# MCU.net
KiCad netlist of a schematic drawn in Altium Designer
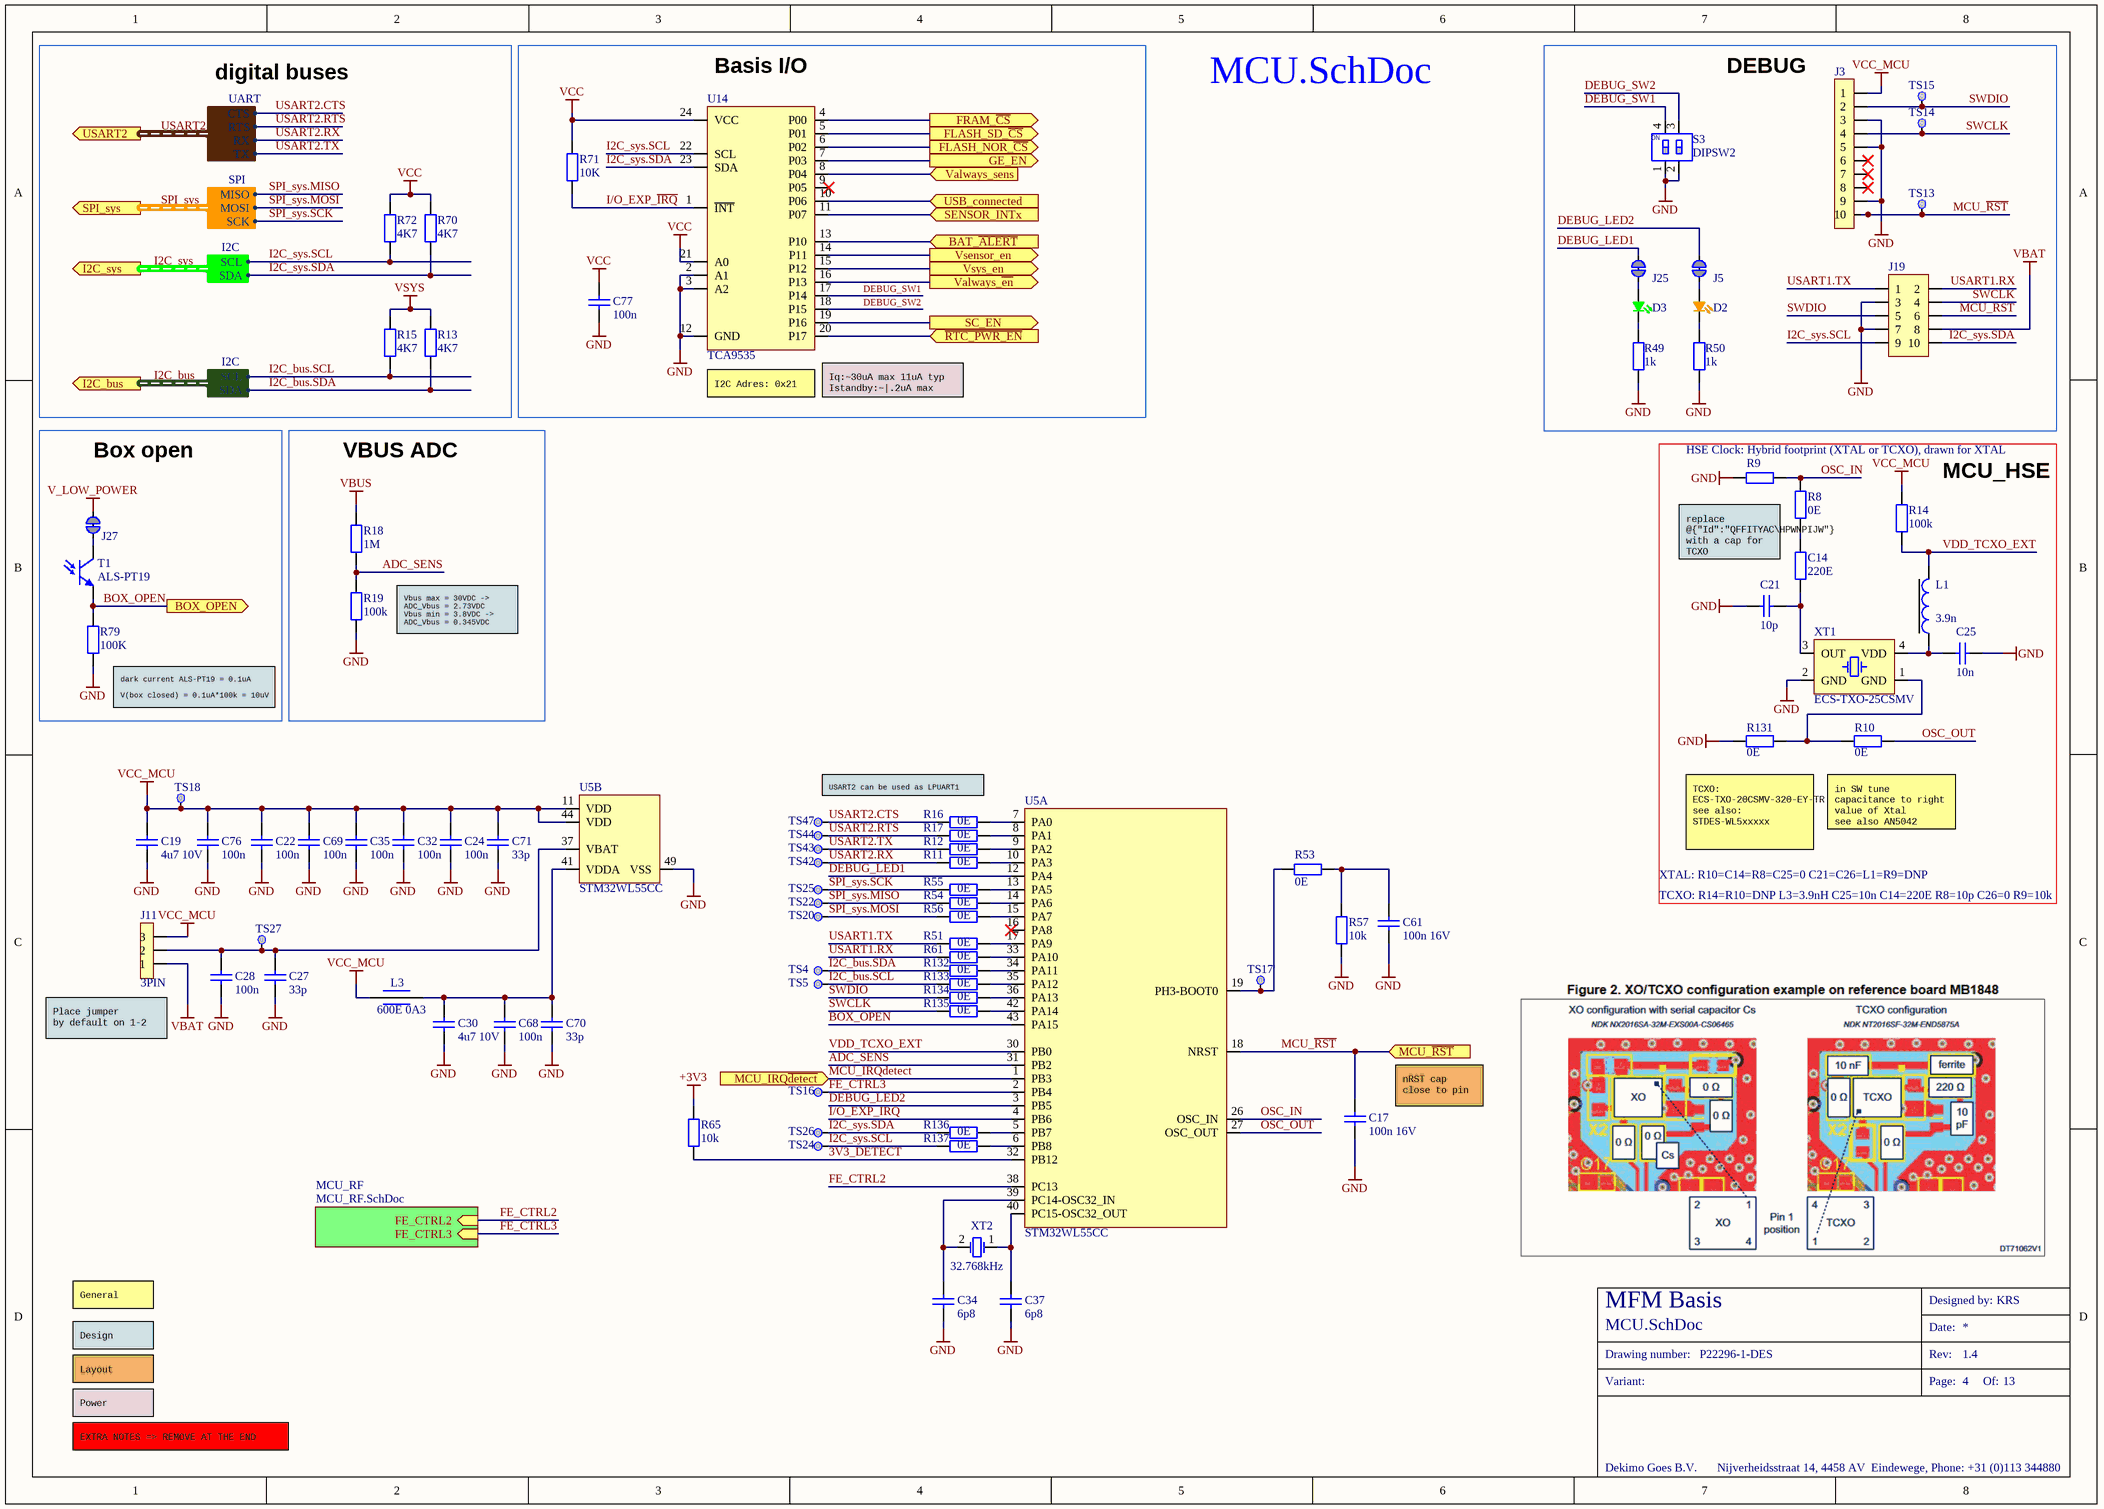
[diagram p0: MCU.SchDoc]

(export (version "E")
  (design (tool "Eeschema 10.0.6"))
  (components
    (comp (ref "C14")
      (value "220E")
      (footprint "RESC1005X04N")
      (description "220ohm 62.5mW 1%")
      (libsource (lib "") (part "Resistor_2"))
    )
    (comp (ref "C17")
      (value "100n 16V")
      (footprint "CAPC1005X05N")
      (description "100nF, 16V, 10%, X7R")
      (libsource (lib "DCI") (part "Capacitor_NP"))
    )
    (comp (ref "C19")
      (value "4u7 10V")
      (footprint "CAPC1608X09N")
      (description "4.7uF 10% 10V X5R")
      (libsource (lib "DCI") (part "Capacitor_NP"))
    )
    (comp (ref "C21")
      (value "10p")
      (footprint "CAPC1005X05N")
      (description "10pF, 50V, 5%, NP0")
      (libsource (lib "DCI") (part "Capacitor_NP"))
    )
    (comp (ref "C22")
      (value "100n")
      (footprint "CAPC1005X05N")
      (description "100nF, 16V, 10%, X7R")
      (libsource (lib "DCI") (part "Capacitor_NP"))
    )
    (comp (ref "C24")
      (value "100n")
      (footprint "CAP-000G001-002")
      (description "100nF, 10V, X5R")
      (libsource (lib "DCI") (part "Capacitor_NP"))
    )
    (comp (ref "C25")
      (value "10n")
      (footprint "CAP-000G001-002")
      (description "10nF, 10V, X7R")
      (libsource (lib "") (part "Capacitor_NP_1"))
    )
    (comp (ref "C27")
      (value "33p")
      (footprint "CAP-000G001-002")
      (description "33pF, 25V, 5%")
      (libsource (lib "DCI") (part "Capacitor_NP"))
    )
    (comp (ref "C28")
      (value "100n")
      (footprint "CAP-000G001-002")
      (description "100nF, 10V, X5R")
      (libsource (lib "DCI") (part "Capacitor_NP"))
    )
    (comp (ref "C30")
      (value "4u7 10V")
      (footprint "CAPC1608X09N")
      (description "4.7uF 10% 10V X5R")
      (libsource (lib "DCI") (part "Capacitor_NP"))
    )
    (comp (ref "C32")
      (value "100n")
      (footprint "CAPC1005X05N")
      (description "100nF, 16V, 10%, X7R")
      (libsource (lib "DCI") (part "Capacitor_NP"))
    )
    (comp (ref "C34")
      (value "6p8")
      (footprint "CAPC1608X09N")
      (description "6p8 +-0.5p 25V NP0")
      (libsource (lib "DCI") (part "Capacitor_NP"))
    )
    (comp (ref "C35")
      (value "100n")
      (footprint "CAPC1005X05N")
      (description "100nF, 16V, 10%, X7R")
      (libsource (lib "DCI") (part "Capacitor_NP"))
    )
    (comp (ref "C37")
      (value "6p8")
      (footprint "CAPC1608X09N")
      (description "6p8 +-0.5p 25V NP0")
      (libsource (lib "DCI") (part "Capacitor_NP"))
    )
    (comp (ref "C61")
      (value "100n 16V")
      (footprint "CAPC1005X05N")
      (description "100nF, 16V, 10%, X7R")
      (libsource (lib "DCI") (part "Capacitor_NP"))
    )
    (comp (ref "C68")
      (value "100n")
      (footprint "CAPC1005X05N")
      (description "100nF, 16V, 10%, X7R")
      (libsource (lib "DCI") (part "Capacitor_NP"))
    )
    (comp (ref "C69")
      (value "100n")
      (footprint "CAPC1005X05N")
      (description "100nF, 16V, 10%, X7R")
      (libsource (lib "DCI") (part "Capacitor_NP"))
    )
    (comp (ref "C70")
      (value "33p")
      (footprint "CAP-000G001-002")
      (description "33pF, 25V, 5%")
      (libsource (lib "DCI") (part "Capacitor_NP"))
    )
    (comp (ref "C71")
      (value "33p")
      (footprint "CAPC1005X05N")
      (description "33pF, 50V, 5%, COG")
      (libsource (lib "DCI") (part "Capacitor_NP"))
    )
    (comp (ref "C76")
      (value "100n")
      (footprint "CAPC1005X05N")
      (description "100nF, 16V, 10%, X7R")
      (libsource (lib "DCI") (part "Capacitor_NP"))
    )
    (comp (ref "C77")
      (value "100n")
      (footprint "CAPC1608X09N")
      (description "100nF 50V 10% X7R")
      (libsource (lib "DCI") (part "Capacitor_NP"))
    )
    (comp (ref "D2")
      (value "~")
      (footprint "LED_0603")
      (description "Led Orange 0603")
      (libsource (lib "DCI") (part "LED_AMBER"))
    )
    (comp (ref "D3")
      (value "~")
      (footprint "LED_0603_ANODE")
      (description "Led Groen 0603")
      (libsource (lib "DCI") (part "LED_GREEN"))
    )
    (comp (ref "J3")
      (value "Harwin Archer M50 Series")
      (footprint "PHDR2X5_SMD_P1.27")
      (description "pinh 2x5/straight/Au/1.27pitch")
      (libsource (lib "DCI") (part "10PIN"))
    )
    (comp (ref "J5")
      (value "~")
      (footprint "Solderbridge NC")
      (description "Solderbridge  - Normally Connected")
      (libsource (lib "PCBComponenten") (part "SolderbridgeNC"))
    )
    (comp (ref "J11")
      (value "3PIN")
      (footprint "CON-003G001-003")
      (description "pinh 1x3/straight/Au/1.27pitch")
      (libsource (lib "DCI") (part "3PIN"))
    )
    (comp (ref "J19")
      (value "~")
      (footprint "PHDR2X5_P2.54")
      (description "pinh 2x5/straight/h=6.7/Au")
      (libsource (lib "DCI") (part "2X5PIN"))
    )
    (comp (ref "J25")
      (value "~")
      (footprint "Solderbridge NC")
      (description "Solderbridge  - Normally Connected")
      (libsource (lib "PCBComponenten") (part "SolderbridgeNC"))
    )
    (comp (ref "J27")
      (value "~")
      (footprint "Solderbridge NC")
      (description "Solderbridge  - Normally Connected")
      (libsource (lib "PCBComponenten") (part "SolderbridgeNC"))
    )
    (comp (ref "L1")
      (value "3.9n")
      (footprint "IND-002G000-002")
      (description "3.9nH 0.1nH 750mA")
      (libsource (lib "DCI") (part "Inductor"))
    )
    (comp (ref "L3")
      (value "600E 0A3")
      (footprint "INDC1608X10N")
      (description "600E @100Mhz 0.3A")
      (libsource (lib "DCI") (part "ferrite"))
    )
    (comp (ref "R8")
      (value "0E")
      (footprint "RESC1005X04N")
      (description "0E, 62.5mW, 1%")
      (libsource (lib "DCI") (part "Resistor"))
    )
    (comp (ref "R9")
      (value "100E")
      (footprint "RESC1005X04N")
      (description "100E, 62.5mW, 1%")
      (libsource (lib "") (part "Resistor_1"))
    )
    (comp (ref "R10")
      (value "0E")
      (footprint "RESC1005X04N")
      (description "0E, 62.5mW, 1%")
      (libsource (lib "") (part "Resistor_1"))
    )
    (comp (ref "R11")
      (value "0E")
      (footprint "RESC1005X04N")
      (description "0E, 62.5mW, 1%")
      (libsource (lib "") (part "Resistor_1"))
    )
    (comp (ref "R12")
      (value "0E")
      (footprint "RESC1005X04N")
      (description "0E, 62.5mW, 1%")
      (libsource (lib "") (part "Resistor_1"))
    )
    (comp (ref "R13")
      (value "4K7")
      (footprint "RESC1005x04N")
      (description "4K7, 62.5mW, 1%")
      (libsource (lib "DCI") (part "Resistor"))
    )
    (comp (ref "R14")
      (value "100k")
      (footprint "RESC1005X04N")
      (description "100K, 62.5mW, 1%")
      (libsource (lib "DCI") (part "Resistor"))
    )
    (comp (ref "R15")
      (value "4K7")
      (footprint "RESC1005x04N")
      (description "4K7, 62.5mW, 1%")
      (libsource (lib "DCI") (part "Resistor"))
    )
    (comp (ref "R16")
      (value "0E")
      (footprint "RESC1005X04N")
      (description "0E, 62.5mW, 1%")
      (libsource (lib "") (part "Resistor_1"))
    )
    (comp (ref "R17")
      (value "0E")
      (footprint "RESC1005X04N")
      (description "0E, 62.5mW, 1%")
      (libsource (lib "") (part "Resistor_1"))
    )
    (comp (ref "R18")
      (value "1M")
      (footprint "RESC1005x04N")
      (description "1M, 62.5mW, 1%")
      (libsource (lib "") (part "Resistor_4"))
    )
    (comp (ref "R19")
      (value "100k")
      (footprint "RESC1005X04N")
      (description "100K, 62.5mW, 1%")
      (libsource (lib "DCI") (part "Resistor"))
    )
    (comp (ref "R49")
      (value "1k")
      (footprint "RESC1608X13N")
      (description "1K, 100mW, 1%")
      (libsource (lib "") (part "Resistor_2"))
    )
    (comp (ref "R50")
      (value "1k")
      (footprint "RESC1608X13N")
      (description "1K, 100mW, 1%")
      (libsource (lib "") (part "Resistor_2"))
    )
    (comp (ref "R51")
      (value "0E")
      (footprint "RESC1005X04N")
      (description "0E, 62.5mW, 1%")
      (libsource (lib "") (part "Resistor_1"))
    )
    (comp (ref "R53")
      (value "0E")
      (footprint "RESC1005X04N")
      (description "0E, 62.5mW, 1%")
      (libsource (lib "") (part "Resistor_3"))
    )
    (comp (ref "R54")
      (value "0E")
      (footprint "RESC1005X04N")
      (description "0E, 62.5mW, 1%")
      (libsource (lib "") (part "Resistor_1"))
    )
    (comp (ref "R55")
      (value "0E")
      (footprint "RESC1005X04N")
      (description "0E, 62.5mW, 1%")
      (libsource (lib "") (part "Resistor_1"))
    )
    (comp (ref "R56")
      (value "0E")
      (footprint "RESC1005X04N")
      (description "0E, 62.5mW, 1%")
      (libsource (lib "") (part "Resistor_1"))
    )
    (comp (ref "R57")
      (value "10k")
      (footprint "RESC1005X04N")
      (description "10K, 62.5mW, 1%")
      (libsource (lib "") (part "Resistor_1"))
    )
    (comp (ref "R61")
      (value "0E")
      (footprint "RESC1005X04N")
      (description "0E, 62.5mW, 1%")
      (libsource (lib "") (part "Resistor_1"))
    )
    (comp (ref "R65")
      (value "10k")
      (footprint "RESC1005X04N")
      (description "10K, 62.5mW, 1%")
      (libsource (lib "") (part "Resistor_1"))
    )
    (comp (ref "R70")
      (value "4K7")
      (footprint "RESC1005x04N")
      (description "4K7, 62.5mW, 1%")
      (libsource (lib "DCI") (part "Resistor"))
    )
    (comp (ref "R71")
      (value "10K")
      (footprint "RESC1608X13N")
      (description "10k 100mW, 1%")
      (libsource (lib "DCI") (part "Resistor"))
    )
    (comp (ref "R72")
      (value "4K7")
      (footprint "RESC1005x04N")
      (description "4K7, 62.5mW, 1%")
      (libsource (lib "DCI") (part "Resistor"))
    )
    (comp (ref "R79")
      (value "100K")
      (footprint "RESC1608X13N")
      (description "100k 100mW, 1%")
      (libsource (lib "DCI") (part "Resistor"))
    )
    (comp (ref "R131")
      (value "0E")
      (footprint "RESC1005X04N")
      (description "0E, 62.5mW, 1%")
      (libsource (lib "") (part "Resistor_1"))
    )
    (comp (ref "R132")
      (value "0E")
      (footprint "RESC1005X04N")
      (description "0E, 62.5mW, 1%")
      (libsource (lib "") (part "Resistor_1"))
    )
    (comp (ref "R133")
      (value "0E")
      (footprint "RESC1005X04N")
      (description "0E, 62.5mW, 1%")
      (libsource (lib "") (part "Resistor_1"))
    )
    (comp (ref "R134")
      (value "0E")
      (footprint "RESC1005X04N")
      (description "0E, 62.5mW, 1%")
      (libsource (lib "") (part "Resistor_1"))
    )
    (comp (ref "R135")
      (value "0E")
      (footprint "RESC1005X04N")
      (description "0E, 62.5mW, 1%")
      (libsource (lib "") (part "Resistor_1"))
    )
    (comp (ref "R136")
      (value "0E")
      (footprint "RESC1005X04N")
      (description "0E, 62.5mW, 1%")
      (libsource (lib "") (part "Resistor_1"))
    )
    (comp (ref "R137")
      (value "0E")
      (footprint "RESC1005X04N")
      (description "0E, 62.5mW, 1%")
      (libsource (lib "") (part "Resistor_1"))
    )
    (comp (ref "S3")
      (value "DIPSW2")
      (footprint "SW_GDH02S04")
      (description "DIP,2p,Straight,H=2,3mm,SMD,AU")
      (libsource (lib "DCI") (part "DIPSW2"))
    )
    (comp (ref "T1")
      (value "ALS-PT19")
      (footprint "SMD-000G001-002")
      (description "Ambient Light Sensor")
      (libsource (lib "DCI") (part "SENS_NPN_Photo"))
    )
    (comp (ref "TS4")
      (value "TESTPAD")
      (footprint "TESTPAD 2MM")
      (description "0.5mm Testpad SMD")
      (libsource (lib "PCBComponenten") (part "TESTPAD"))
    )
    (comp (ref "TS5")
      (value "TESTPAD")
      (footprint "TESTPAD 2MM")
      (description "0.5mm Testpad SMD")
      (libsource (lib "PCBComponenten") (part "TESTPAD"))
    )
    (comp (ref "TS13")
      (value "TESTPAD")
      (footprint "TESTPAD 2MM")
      (description "0.5mm Testpad SMD")
      (libsource (lib "PCBComponenten") (part "TESTPAD"))
    )
    (comp (ref "TS14")
      (value "TESTPAD")
      (footprint "TESTPAD 2MM")
      (description "0.5mm Testpad SMD")
      (libsource (lib "PCBComponenten") (part "TESTPAD"))
    )
    (comp (ref "TS15")
      (value "TESTPAD")
      (footprint "TESTPAD 2MM")
      (description "0.5mm Testpad SMD")
      (libsource (lib "PCBComponenten") (part "TESTPAD"))
    )
    (comp (ref "TS16")
      (value "TESTPAD")
      (footprint "TESTPAD 2MM")
      (description "0.5mm Testpad SMD")
      (libsource (lib "PCBComponenten") (part "TESTPAD"))
    )
    (comp (ref "TS17")
      (value "TESTPAD")
      (footprint "TESTPAD 2MM")
      (description "0.5mm Testpad SMD")
      (libsource (lib "PCBComponenten") (part "TESTPAD"))
    )
    (comp (ref "TS18")
      (value "TESTPAD")
      (footprint "TESTPAD 2MM")
      (description "0.5mm Testpad SMD")
      (libsource (lib "PCBComponenten") (part "TESTPAD"))
    )
    (comp (ref "TS20")
      (value "TESTPAD")
      (footprint "TESTPAD 2MM")
      (description "0.5mm Testpad SMD")
      (libsource (lib "PCBComponenten") (part "TESTPAD"))
    )
    (comp (ref "TS22")
      (value "TESTPAD")
      (footprint "TESTPAD 2MM")
      (description "0.5mm Testpad SMD")
      (libsource (lib "PCBComponenten") (part "TESTPAD"))
    )
    (comp (ref "TS24")
      (value "TESTPAD")
      (footprint "TESTPAD 2MM")
      (description "0.5mm Testpad SMD")
      (libsource (lib "PCBComponenten") (part "TESTPAD"))
    )
    (comp (ref "TS25")
      (value "TESTPAD")
      (footprint "TESTPAD 2MM")
      (description "0.5mm Testpad SMD")
      (libsource (lib "PCBComponenten") (part "TESTPAD"))
    )
    (comp (ref "TS26")
      (value "TESTPAD")
      (footprint "TESTPAD 2MM")
      (description "0.5mm Testpad SMD")
      (libsource (lib "PCBComponenten") (part "TESTPAD"))
    )
    (comp (ref "TS27")
      (value "TESTPAD")
      (footprint "TESTPAD 2MM")
      (description "0.5mm Testpad SMD")
      (libsource (lib "PCBComponenten") (part "TESTPAD"))
    )
    (comp (ref "TS42")
      (value "TESTPAD")
      (footprint "TESTPAD 2MM")
      (description "0.5mm Testpad SMD")
      (libsource (lib "PCBComponenten") (part "TESTPAD"))
    )
    (comp (ref "TS43")
      (value "TESTPAD")
      (footprint "TESTPAD 2MM")
      (description "0.5mm Testpad SMD")
      (libsource (lib "PCBComponenten") (part "TESTPAD"))
    )
    (comp (ref "TS44")
      (value "TESTPAD")
      (footprint "TESTPAD 2MM")
      (description "0.5mm Testpad SMD")
      (libsource (lib "PCBComponenten") (part "TESTPAD"))
    )
    (comp (ref "TS47")
      (value "TESTPAD")
      (footprint "TESTPAD 2MM")
      (description "0.5mm Testpad SMD")
      (libsource (lib "PCBComponenten") (part "TESTPAD"))
    )
    (comp (ref "U5")
      (value "STM32WL55CC")
      (footprint "QFN-500G000-048")
      (libsource (lib "DCI") (part "STM32WL55"))
    )
    (comp (ref "U14")
      (value "TCA9535")
      (footprint "SOP-650001-024")
      (description "16-bits  I2C I/O Expander")
      (libsource (lib "DCI") (part "IO_EXPANDER_TCA9535"))
    )
    (comp (ref "XT1")
      (value "ECS-TXO-25CSMV")
      (footprint "XTL-001G001-004")
      (description "32Mhz 1V7-3V465 2x1.6mm")
      (libsource (lib "DCI") (part "OSC_4P"))
    )
    (comp (ref "XT2")
      (value "32.768kHz")
      (footprint "CHIP2PINSM127P600-8N")
      (description "32.768kHz 20ppm 12.5pF")
      (libsource (lib "DCI") (part "XTAL"))
    )
  )
  (nets
    (net (code "5") (name "+3V3") (class "Default")
      (node (ref "R65") (pin "2") (pinfunction "2_2") (pintype "passive"))
    )
    (net (code "6") (name "/3V3_DETECT") (class "Default")
      (node (ref "R65") (pin "1") (pinfunction "1_1") (pintype "passive"))
      (node (ref "U5") (pin "32") (pinfunction "PB12_32") (pintype "passive"))
    )
    (net (code "7") (name "/ADC_SENS") (class "Default")
      (node (ref "R18") (pin "2") (pinfunction "2_2") (pintype "passive"))
      (node (ref "R19") (pin "2") (pinfunction "2_2") (pintype "passive"))
      (node (ref "U5") (pin "31") (pinfunction "PB2_31") (pintype "passive"))
    )
    (net (code "8") (name "/BAT_~{ALERT}") (class "Default")
      (node (ref "U14") (pin "13") (pinfunction "P10_13") (pintype "passive"))
    )
    (net (code "9") (name "/BOX_OPEN") (class "Default")
      (node (ref "R79") (pin "2") (pinfunction "2_2") (pintype "passive"))
      (node (ref "T1") (pin "2") (pinfunction "2_2") (pintype "passive"))
      (node (ref "U5") (pin "43") (pinfunction "PA15_43") (pintype "passive"))
    )
    (net (code "10") (name "/DEBUG_LED1") (class "Default")
      (node (ref "J25") (pin "2") (pinfunction "2_2") (pintype "passive"))
      (node (ref "U5") (pin "12") (pinfunction "PA4_12") (pintype "passive"))
    )
    (net (code "11") (name "/DEBUG_LED2") (class "Default")
      (node (ref "J5") (pin "2") (pinfunction "2_2") (pintype "passive"))
      (node (ref "U5") (pin "3") (pinfunction "PB5_3") (pintype "passive"))
    )
    (net (code "12") (name "/DEBUG_SW1") (class "Default")
      (node (ref "S3") (pin "4") (pinfunction "B1_4") (pintype "passive"))
      (node (ref "U14") (pin "17") (pinfunction "P14_17") (pintype "passive"))
    )
    (net (code "13") (name "/DEBUG_SW2") (class "Default")
      (node (ref "S3") (pin "3") (pinfunction "B2_3") (pintype "passive"))
      (node (ref "U14") (pin "18") (pinfunction "P15_18") (pintype "passive"))
    )
    (net (code "14") (name "/FE_CTRL2") (class "Default")
      (node (ref "U5") (pin "38") (pinfunction "PC13_38") (pintype "passive"))
    )
    (net (code "15") (name "/FE_CTRL3") (class "Default")
      (node (ref "TS16") (pin "1") (pinfunction "TP_1") (pintype "passive"))
      (node (ref "U5") (pin "2") (pinfunction "PB4_2") (pintype "passive"))
    )
    (net (code "16") (name "/FLASH_NOR_~{CS}") (class "Default")
      (node (ref "U14") (pin "6") (pinfunction "P02_6") (pintype "passive"))
    )
    (net (code "17") (name "/FLASH_SD_~{CS}") (class "Default")
      (node (ref "U14") (pin "5") (pinfunction "P01_5") (pintype "passive"))
    )
    (net (code "18") (name "/FRAM_~{CS}") (class "Default")
      (node (ref "U14") (pin "4") (pinfunction "P00_4") (pintype "passive"))
    )
    (net (code "19") (name "/GE_EN") (class "Default")
      (node (ref "U14") (pin "7") (pinfunction "P03_7") (pintype "passive"))
    )
    (net (code "20") (name "/I2C_bus.SCL") (class "Default")
      (node (ref "R133") (pin "1") (pinfunction "1_1") (pintype "passive"))
      (node (ref "R15") (pin "1") (pinfunction "1_1") (pintype "passive"))
      (node (ref "TS5") (pin "1") (pinfunction "TP_1") (pintype "passive"))
    )
    (net (code "21") (name "/I2C_bus.SDA") (class "Default")
      (node (ref "R13") (pin "1") (pinfunction "1_1") (pintype "passive"))
      (node (ref "R132") (pin "1") (pinfunction "1_1") (pintype "passive"))
      (node (ref "TS4") (pin "1") (pinfunction "TP_1") (pintype "passive"))
    )
    (net (code "23") (name "/I2C_sys.SCL") (class "Default")
      (node (ref "J19") (pin "9") (pinfunction "9_9") (pintype "passive"))
      (node (ref "R137") (pin "1") (pinfunction "1_1") (pintype "passive"))
      (node (ref "R72") (pin "1") (pinfunction "1_1") (pintype "passive"))
      (node (ref "TS24") (pin "1") (pinfunction "TP_1") (pintype "passive"))
      (node (ref "U14") (pin "22") (pinfunction "SCL_22") (pintype "passive"))
    )
    (net (code "24") (name "/I2C_sys.SDA") (class "Default")
      (node (ref "J19") (pin "10") (pinfunction "10_10") (pintype "passive"))
      (node (ref "R136") (pin "1") (pinfunction "1_1") (pintype "passive"))
      (node (ref "R70") (pin "1") (pinfunction "1_1") (pintype "passive"))
      (node (ref "TS26") (pin "1") (pinfunction "TP_1") (pintype "passive"))
      (node (ref "U14") (pin "23") (pinfunction "SDA_23") (pintype "passive"))
    )
    (net (code "26") (name "/I{slash}O_EXP_~{IRQ}") (class "Default")
      (node (ref "R71") (pin "1") (pinfunction "1_1") (pintype "passive"))
      (node (ref "U14") (pin "1") (pinfunction "~{INT}_1") (pintype "passive"))
      (node (ref "U5") (pin "4") (pinfunction "PB6_4") (pintype "passive"))
    )
    (net (code "27") (name "/MCU_IRQ~{detect}") (class "Default")
      (node (ref "U5") (pin "1") (pinfunction "PB3_1") (pintype "passive"))
    )
    (net (code "28") (name "/MCU_~{RST}") (class "Default")
      (node (ref "C17") (pin "2") (pinfunction "2_2") (pintype "passive"))
      (node (ref "J19") (pin "6") (pinfunction "6_6") (pintype "passive"))
      (node (ref "J3") (pin "10") (pinfunction "10_10") (pintype "passive"))
      (node (ref "TS13") (pin "1") (pinfunction "TP_1") (pintype "passive"))
      (node (ref "U5") (pin "18") (pinfunction "NRST_18") (pintype "passive"))
    )
    (net (code "29") (name "/OSC_IN") (class "Default")
      (node (ref "R8") (pin "2") (pinfunction "2_2") (pintype "passive"))
      (node (ref "R9") (pin "2") (pinfunction "2_2") (pintype "passive"))
      (node (ref "U5") (pin "26") (pinfunction "OSC_IN_26") (pintype "passive"))
    )
    (net (code "30") (name "/OSC_OUT") (class "Default")
      (node (ref "R10") (pin "2") (pinfunction "2_2") (pintype "passive"))
      (node (ref "U5") (pin "27") (pinfunction "OSC_OUT_27") (pintype "passive"))
    )
    (net (code "31") (name "/SC_EN") (class "Default")
      (node (ref "U14") (pin "19") (pinfunction "P16_19") (pintype "passive"))
    )
    (net (code "32") (name "/SENSOR_INTx") (class "Default")
      (node (ref "U14") (pin "11") (pinfunction "P07_11") (pintype "passive"))
    )
    (net (code "33") (name "/SPI_sys.MISO") (class "Default")
      (node (ref "R54") (pin "1") (pinfunction "1_1") (pintype "passive"))
      (node (ref "TS22") (pin "1") (pinfunction "TP_1") (pintype "passive"))
    )
    (net (code "34") (name "/SPI_sys.MOSI") (class "Default")
      (node (ref "R56") (pin "1") (pinfunction "1_1") (pintype "passive"))
      (node (ref "TS20") (pin "1") (pinfunction "TP_1") (pintype "passive"))
    )
    (net (code "35") (name "/SPI_sys.SCK") (class "Default")
      (node (ref "R55") (pin "1") (pinfunction "1_1") (pintype "passive"))
      (node (ref "TS25") (pin "1") (pinfunction "TP_1") (pintype "passive"))
    )
    (net (code "37") (name "/SWCLK") (class "Default")
      (node (ref "J19") (pin "4") (pinfunction "4_4") (pintype "passive"))
      (node (ref "J3") (pin "4") (pinfunction "4_4") (pintype "passive"))
      (node (ref "R135") (pin "1") (pinfunction "1_1") (pintype "passive"))
      (node (ref "TS14") (pin "1") (pinfunction "TP_1") (pintype "passive"))
    )
    (net (code "38") (name "/SWDIO") (class "Default")
      (node (ref "J19") (pin "5") (pinfunction "5_5") (pintype "passive"))
      (node (ref "J3") (pin "2") (pinfunction "2_2") (pintype "passive"))
      (node (ref "R134") (pin "1") (pinfunction "1_1") (pintype "passive"))
      (node (ref "TS15") (pin "1") (pinfunction "TP_1") (pintype "passive"))
    )
    (net (code "39") (name "/USART1.RX") (class "Default")
      (node (ref "J19") (pin "2") (pinfunction "2_2") (pintype "passive"))
      (node (ref "R61") (pin "1") (pinfunction "1_1") (pintype "passive"))
    )
    (net (code "40") (name "/USART1.TX") (class "Default")
      (node (ref "J19") (pin "1") (pinfunction "1_1") (pintype "passive"))
      (node (ref "R51") (pin "1") (pinfunction "1_1") (pintype "passive"))
    )
    (net (code "41") (name "/USART2.CTS") (class "Default")
      (node (ref "R16") (pin "1") (pinfunction "1_1") (pintype "passive"))
      (node (ref "TS47") (pin "1") (pinfunction "TP_1") (pintype "passive"))
    )
    (net (code "42") (name "/USART2.RTS") (class "Default")
      (node (ref "R17") (pin "1") (pinfunction "1_1") (pintype "passive"))
      (node (ref "TS44") (pin "1") (pinfunction "TP_1") (pintype "passive"))
    )
    (net (code "43") (name "/USART2.RX") (class "Default")
      (node (ref "R11") (pin "1") (pinfunction "1_1") (pintype "passive"))
      (node (ref "TS42") (pin "1") (pinfunction "TP_1") (pintype "passive"))
    )
    (net (code "44") (name "/USART2.TX") (class "Default")
      (node (ref "R12") (pin "1") (pinfunction "1_1") (pintype "passive"))
      (node (ref "TS43") (pin "1") (pinfunction "TP_1") (pintype "passive"))
    )
    (net (code "46") (name "/USB_connected") (class "Default")
      (node (ref "U14") (pin "10") (pinfunction "P06_10") (pintype "passive"))
    )
    (net (code "47") (name "/VDD_TCXO_EXT") (class "Default")
      (node (ref "L1") (pin "2") (pinfunction "2_2") (pintype "passive"))
      (node (ref "R14") (pin "1") (pinfunction "1_1") (pintype "passive"))
      (node (ref "U5") (pin "30") (pinfunction "PB0_30") (pintype "passive"))
    )
    (net (code "48") (name "/Valways_sens") (class "Default")
      (node (ref "U14") (pin "8") (pinfunction "P04_8") (pintype "passive"))
    )
    (net (code "49") (name "/Valways_~{en}") (class "Default")
      (node (ref "U14") (pin "16") (pinfunction "P13_16") (pintype "passive"))
    )
    (net (code "50") (name "/Vsensor_en") (class "Default")
      (node (ref "U14") (pin "14") (pinfunction "P11_14") (pintype "passive"))
    )
    (net (code "51") (name "/Vsys_en") (class "Default")
      (node (ref "U14") (pin "15") (pinfunction "P12_15") (pintype "passive"))
    )
    (net (code "52") (name "/~{RTC_PWR_EN}") (class "Default")
      (node (ref "U14") (pin "20") (pinfunction "P17_20") (pintype "passive"))
    )
    (net (code "53") (name "GND") (class "Default")
      (node (ref "C17") (pin "1") (pinfunction "1_1") (pintype "passive"))
      (node (ref "C19") (pin "1") (pinfunction "1_1") (pintype "passive"))
      (node (ref "C21") (pin "1") (pinfunction "1_1") (pintype "passive"))
      (node (ref "C22") (pin "1") (pinfunction "1_1") (pintype "passive"))
      (node (ref "C24") (pin "1") (pinfunction "1_1") (pintype "passive"))
      (node (ref "C25") (pin "1") (pinfunction "1_1") (pintype "passive"))
      (node (ref "C27") (pin "1") (pinfunction "1_1") (pintype "passive"))
      (node (ref "C28") (pin "1") (pinfunction "1_1") (pintype "passive"))
      (node (ref "C30") (pin "1") (pinfunction "1_1") (pintype "passive"))
      (node (ref "C32") (pin "1") (pinfunction "1_1") (pintype "passive"))
      (node (ref "C34") (pin "1") (pinfunction "1_1") (pintype "passive"))
      (node (ref "C35") (pin "1") (pinfunction "1_1") (pintype "passive"))
      (node (ref "C37") (pin "1") (pinfunction "1_1") (pintype "passive"))
      (node (ref "C61") (pin "1") (pinfunction "1_1") (pintype "passive"))
      (node (ref "C68") (pin "1") (pinfunction "1_1") (pintype "passive"))
      (node (ref "C69") (pin "1") (pinfunction "1_1") (pintype "passive"))
      (node (ref "C70") (pin "1") (pinfunction "1_1") (pintype "passive"))
      (node (ref "C71") (pin "1") (pinfunction "1_1") (pintype "passive"))
      (node (ref "C76") (pin "1") (pinfunction "1_1") (pintype "passive"))
      (node (ref "C77") (pin "1") (pinfunction "1_1") (pintype "passive"))
      (node (ref "J19") (pin "3") (pinfunction "3_3") (pintype "passive"))
      (node (ref "J19") (pin "7") (pinfunction "7_7") (pintype "passive"))
      (node (ref "J3") (pin "3") (pinfunction "3_3") (pintype "passive"))
      (node (ref "J3") (pin "5") (pinfunction "5_5") (pintype "passive"))
      (node (ref "J3") (pin "9") (pinfunction "9_9") (pintype "passive"))
      (node (ref "R131") (pin "1") (pinfunction "1_1") (pintype "passive"))
      (node (ref "R19") (pin "1") (pinfunction "1_1") (pintype "passive"))
      (node (ref "R49") (pin "1") (pinfunction "1_1") (pintype "passive"))
      (node (ref "R50") (pin "1") (pinfunction "1_1") (pintype "passive"))
      (node (ref "R57") (pin "1") (pinfunction "1_1") (pintype "passive"))
      (node (ref "R79") (pin "1") (pinfunction "1_1") (pintype "passive"))
      (node (ref "R9") (pin "1") (pinfunction "1_1") (pintype "passive"))
      (node (ref "S3") (pin "1") (pinfunction "A1_1") (pintype "passive"))
      (node (ref "S3") (pin "2") (pinfunction "A2_2") (pintype "passive"))
      (node (ref "U14") (pin "12") (pinfunction "GND_12") (pintype "passive"))
      (node (ref "U14") (pin "2") (pinfunction "A1_2") (pintype "passive"))
      (node (ref "U14") (pin "3") (pinfunction "A2_3") (pintype "passive"))
      (node (ref "U5") (pin "49") (pinfunction "VSS_49") (pintype "passive"))
      (node (ref "XT1") (pin "2") (pinfunction "GND_2") (pintype "passive"))
    )
    (net (code "54") (name "Net-(C14-Pad2)") (class "Default")
      (node (ref "C14") (pin "2") (pinfunction "2_2") (pintype "passive"))
      (node (ref "R8") (pin "1") (pinfunction "1_1") (pintype "passive"))
    )
    (net (code "55") (name "Net-(C61-Pad2)") (class "Default")
      (node (ref "C61") (pin "2") (pinfunction "2_2") (pintype "passive"))
      (node (ref "R53") (pin "1") (pinfunction "1_1") (pintype "passive"))
      (node (ref "R57") (pin "2") (pinfunction "2_2") (pintype "passive"))
    )
    (net (code "56") (name "Net-(D2-PadA)") (class "Default")
      (node (ref "D2") (pin "A") (pinfunction "A_A") (pintype "passive"))
      (node (ref "J5") (pin "1") (pinfunction "1_1") (pintype "passive"))
    )
    (net (code "57") (name "Net-(D2-PadC)") (class "Default")
      (node (ref "D2") (pin "C") (pinfunction "C_C") (pintype "passive"))
      (node (ref "R50") (pin "2") (pinfunction "2_2") (pintype "passive"))
    )
    (net (code "58") (name "Net-(D3-PadA)") (class "Default")
      (node (ref "D3") (pin "A") (pinfunction "A_A") (pintype "passive"))
      (node (ref "J25") (pin "1") (pinfunction "1_1") (pintype "passive"))
    )
    (net (code "59") (name "Net-(D3-PadC)") (class "Default")
      (node (ref "D3") (pin "C") (pinfunction "C_C") (pintype "passive"))
      (node (ref "R49") (pin "2") (pinfunction "2_2") (pintype "passive"))
    )
    (net (code "60") (name "Net-(J27-Pad1)") (class "Default")
      (node (ref "J27") (pin "1") (pinfunction "1_1") (pintype "passive"))
      (node (ref "T1") (pin "1") (pinfunction "1_1") (pintype "passive"))
    )
    (net (code "61") (name "Net-(R10-Pad1)") (class "Default")
      (node (ref "R10") (pin "1") (pinfunction "1_1") (pintype "passive"))
      (node (ref "R131") (pin "2") (pinfunction "2_2") (pintype "passive"))
      (node (ref "XT1") (pin "1") (pinfunction "GND_1") (pintype "passive"))
    )
    (net (code "62") (name "Net-(TS17-TP)") (class "Default")
      (node (ref "R53") (pin "2") (pinfunction "2_2") (pintype "passive"))
      (node (ref "TS17") (pin "1") (pinfunction "TP_1") (pintype "passive"))
      (node (ref "U5") (pin "19") (pinfunction "PH3-BOOT0_19") (pintype "passive"))
    )
    (net (code "63") (name "Net-(TS27-TP)") (class "Default")
      (node (ref "C27") (pin "2") (pinfunction "2_2") (pintype "passive"))
      (node (ref "C28") (pin "2") (pinfunction "2_2") (pintype "passive"))
      (node (ref "J11") (pin "2") (pinfunction "2_2") (pintype "passive"))
      (node (ref "TS27") (pin "1") (pinfunction "TP_1") (pintype "passive"))
      (node (ref "U5") (pin "37") (pinfunction "VBAT_37") (pintype "passive"))
    )
    (net (code "64") (name "Net-(U5A-PA0)") (class "Default")
      (node (ref "R16") (pin "2") (pinfunction "2_2") (pintype "passive"))
      (node (ref "U5") (pin "7") (pinfunction "PA0_7") (pintype "passive"))
    )
    (net (code "65") (name "Net-(U5A-PA1)") (class "Default")
      (node (ref "R17") (pin "2") (pinfunction "2_2") (pintype "passive"))
      (node (ref "U5") (pin "8") (pinfunction "PA1_8") (pintype "passive"))
    )
    (net (code "66") (name "Net-(U5A-PA2)") (class "Default")
      (node (ref "R12") (pin "2") (pinfunction "2_2") (pintype "passive"))
      (node (ref "U5") (pin "9") (pinfunction "PA2_9") (pintype "passive"))
    )
    (net (code "67") (name "Net-(U5A-PA3)") (class "Default")
      (node (ref "R11") (pin "2") (pinfunction "2_2") (pintype "passive"))
      (node (ref "U5") (pin "10") (pinfunction "PA3_10") (pintype "passive"))
    )
    (net (code "68") (name "Net-(U5A-PA5)") (class "Default")
      (node (ref "R55") (pin "2") (pinfunction "2_2") (pintype "passive"))
      (node (ref "U5") (pin "13") (pinfunction "PA5_13") (pintype "passive"))
    )
    (net (code "69") (name "Net-(U5A-PA6)") (class "Default")
      (node (ref "R54") (pin "2") (pinfunction "2_2") (pintype "passive"))
      (node (ref "U5") (pin "14") (pinfunction "PA6_14") (pintype "passive"))
    )
    (net (code "70") (name "Net-(U5A-PA7)") (class "Default")
      (node (ref "R56") (pin "2") (pinfunction "2_2") (pintype "passive"))
      (node (ref "U5") (pin "15") (pinfunction "PA7_15") (pintype "passive"))
    )
    (net (code "71") (name "Net-(U5A-PA9)") (class "Default")
      (node (ref "R51") (pin "2") (pinfunction "2_2") (pintype "passive"))
      (node (ref "U5") (pin "17") (pinfunction "PA9_17") (pintype "passive"))
    )
    (net (code "72") (name "Net-(U5A-PA10)") (class "Default")
      (node (ref "R61") (pin "2") (pinfunction "2_2") (pintype "passive"))
      (node (ref "U5") (pin "33") (pinfunction "PA10_33") (pintype "passive"))
    )
    (net (code "73") (name "Net-(U5A-PA11)") (class "Default")
      (node (ref "R132") (pin "2") (pinfunction "2_2") (pintype "passive"))
      (node (ref "U5") (pin "34") (pinfunction "PA11_34") (pintype "passive"))
    )
    (net (code "74") (name "Net-(U5A-PA12)") (class "Default")
      (node (ref "R133") (pin "2") (pinfunction "2_2") (pintype "passive"))
      (node (ref "U5") (pin "35") (pinfunction "PA12_35") (pintype "passive"))
    )
    (net (code "75") (name "Net-(U5A-PA13)") (class "Default")
      (node (ref "R134") (pin "2") (pinfunction "2_2") (pintype "passive"))
      (node (ref "U5") (pin "36") (pinfunction "PA13_36") (pintype "passive"))
    )
    (net (code "76") (name "Net-(U5A-PA14)") (class "Default")
      (node (ref "R135") (pin "2") (pinfunction "2_2") (pintype "passive"))
      (node (ref "U5") (pin "42") (pinfunction "PA14_42") (pintype "passive"))
    )
    (net (code "77") (name "Net-(U5A-PB7)") (class "Default")
      (node (ref "R136") (pin "2") (pinfunction "2_2") (pintype "passive"))
      (node (ref "U5") (pin "5") (pinfunction "PB7_5") (pintype "passive"))
    )
    (net (code "78") (name "Net-(U5A-PB8)") (class "Default")
      (node (ref "R137") (pin "2") (pinfunction "2_2") (pintype "passive"))
      (node (ref "U5") (pin "6") (pinfunction "PB8_6") (pintype "passive"))
    )
    (net (code "79") (name "Net-(U5A-PC14-OSC32_IN)") (class "Default")
      (node (ref "C34") (pin "2") (pinfunction "2_2") (pintype "passive"))
      (node (ref "U5") (pin "39") (pinfunction "PC14-OSC32_IN_39") (pintype "passive"))
      (node (ref "XT2") (pin "2") (pinfunction "OSC2_2") (pintype "passive"))
    )
    (net (code "80") (name "Net-(U5A-PC15-OSC32_OUT)") (class "Default")
      (node (ref "C37") (pin "2") (pinfunction "2_2") (pintype "passive"))
      (node (ref "U5") (pin "40") (pinfunction "PC15-OSC32_OUT_40") (pintype "passive"))
      (node (ref "XT2") (pin "1") (pinfunction "OSC1_1") (pintype "passive"))
    )
    (net (code "81") (name "Net-(U5B-VDDA)") (class "Default")
      (node (ref "C30") (pin "2") (pinfunction "2_2") (pintype "passive"))
      (node (ref "C68") (pin "2") (pinfunction "2_2") (pintype "passive"))
      (node (ref "C70") (pin "2") (pinfunction "2_2") (pintype "passive"))
      (node (ref "L3") (pin "2") (pinfunction "2_2") (pintype "passive"))
      (node (ref "U5") (pin "41") (pinfunction "VDDA_41") (pintype "passive"))
    )
    (net (code "82") (name "Net-(XT1-OUT)") (class "Default")
      (node (ref "C14") (pin "1") (pinfunction "1_1") (pintype "passive"))
      (node (ref "C21") (pin "2") (pinfunction "2_2") (pintype "passive"))
      (node (ref "XT1") (pin "3") (pinfunction "OUT_3") (pintype "passive"))
    )
    (net (code "83") (name "Net-(XT1-VDD)") (class "Default")
      (node (ref "C25") (pin "2") (pinfunction "2_2") (pintype "passive"))
      (node (ref "L1") (pin "1") (pinfunction "1_1") (pintype "passive"))
      (node (ref "XT1") (pin "4") (pinfunction "VDD_4") (pintype "passive"))
    )
    (net (code "84") (name "VBAT") (class "Default")
      (node (ref "J11") (pin "1") (pinfunction "1_1") (pintype "passive"))
      (node (ref "J19") (pin "8") (pinfunction "8_8") (pintype "passive"))
    )
    (net (code "85") (name "VBUS") (class "Default")
      (node (ref "R18") (pin "1") (pinfunction "1_1") (pintype "passive"))
    )
    (net (code "86") (name "VCC") (class "Default")
      (node (ref "C77") (pin "2") (pinfunction "2_2") (pintype "passive"))
      (node (ref "R70") (pin "2") (pinfunction "2_2") (pintype "passive"))
      (node (ref "R71") (pin "2") (pinfunction "2_2") (pintype "passive"))
      (node (ref "R72") (pin "2") (pinfunction "2_2") (pintype "passive"))
      (node (ref "U14") (pin "21") (pinfunction "A0_21") (pintype "passive"))
      (node (ref "U14") (pin "24") (pinfunction "VCC_24") (pintype "passive"))
    )
    (net (code "87") (name "VCC_MCU") (class "Default")
      (node (ref "C19") (pin "2") (pinfunction "2_2") (pintype "passive"))
      (node (ref "C22") (pin "2") (pinfunction "2_2") (pintype "passive"))
      (node (ref "C24") (pin "2") (pinfunction "2_2") (pintype "passive"))
      (node (ref "C32") (pin "2") (pinfunction "2_2") (pintype "passive"))
      (node (ref "C35") (pin "2") (pinfunction "2_2") (pintype "passive"))
      (node (ref "C69") (pin "2") (pinfunction "2_2") (pintype "passive"))
      (node (ref "C71") (pin "2") (pinfunction "2_2") (pintype "passive"))
      (node (ref "C76") (pin "2") (pinfunction "2_2") (pintype "passive"))
      (node (ref "J11") (pin "3") (pinfunction "3_3") (pintype "passive"))
      (node (ref "J3") (pin "1") (pinfunction "1_1") (pintype "passive"))
      (node (ref "L3") (pin "1") (pinfunction "1_1") (pintype "passive"))
      (node (ref "R14") (pin "2") (pinfunction "2_2") (pintype "passive"))
      (node (ref "TS18") (pin "1") (pinfunction "TP_1") (pintype "passive"))
      (node (ref "U5") (pin "11") (pinfunction "VDD_11") (pintype "passive"))
      (node (ref "U5") (pin "44") (pinfunction "VDD_44") (pintype "passive"))
    )
    (net (code "88") (name "VSYS") (class "Default")
      (node (ref "R13") (pin "2") (pinfunction "2_2") (pintype "passive"))
      (node (ref "R15") (pin "2") (pinfunction "2_2") (pintype "passive"))
    )
    (net (code "89") (name "V_LOW_POWER") (class "Default")
      (node (ref "J27") (pin "2") (pinfunction "2_2") (pintype "passive"))
    )
    (net (code "90") (name "unconnected-(J3-Pad6)") (class "Default")
      (node (ref "J3") (pin "6") (pinfunction "6_6") (pintype "passive+no_connect"))
    )
    (net (code "91") (name "unconnected-(J3-Pad7)") (class "Default")
      (node (ref "J3") (pin "7") (pinfunction "7_7") (pintype "passive+no_connect"))
    )
    (net (code "92") (name "unconnected-(J3-Pad8)") (class "Default")
      (node (ref "J3") (pin "8") (pinfunction "8_8") (pintype "passive+no_connect"))
    )
    (net (code "93") (name "unconnected-(U5A-PA8-Pad16)") (class "Default")
      (node (ref "U5") (pin "16") (pinfunction "PA8_16") (pintype "passive+no_connect"))
    )
    (net (code "94") (name "unconnected-(U14-P05-Pad9)") (class "Default")
      (node (ref "U14") (pin "9") (pinfunction "P05_9") (pintype "passive+no_connect"))
    )
  )
)
